# design.net
KiCad netlist of a schematic drawn in Altium Designer
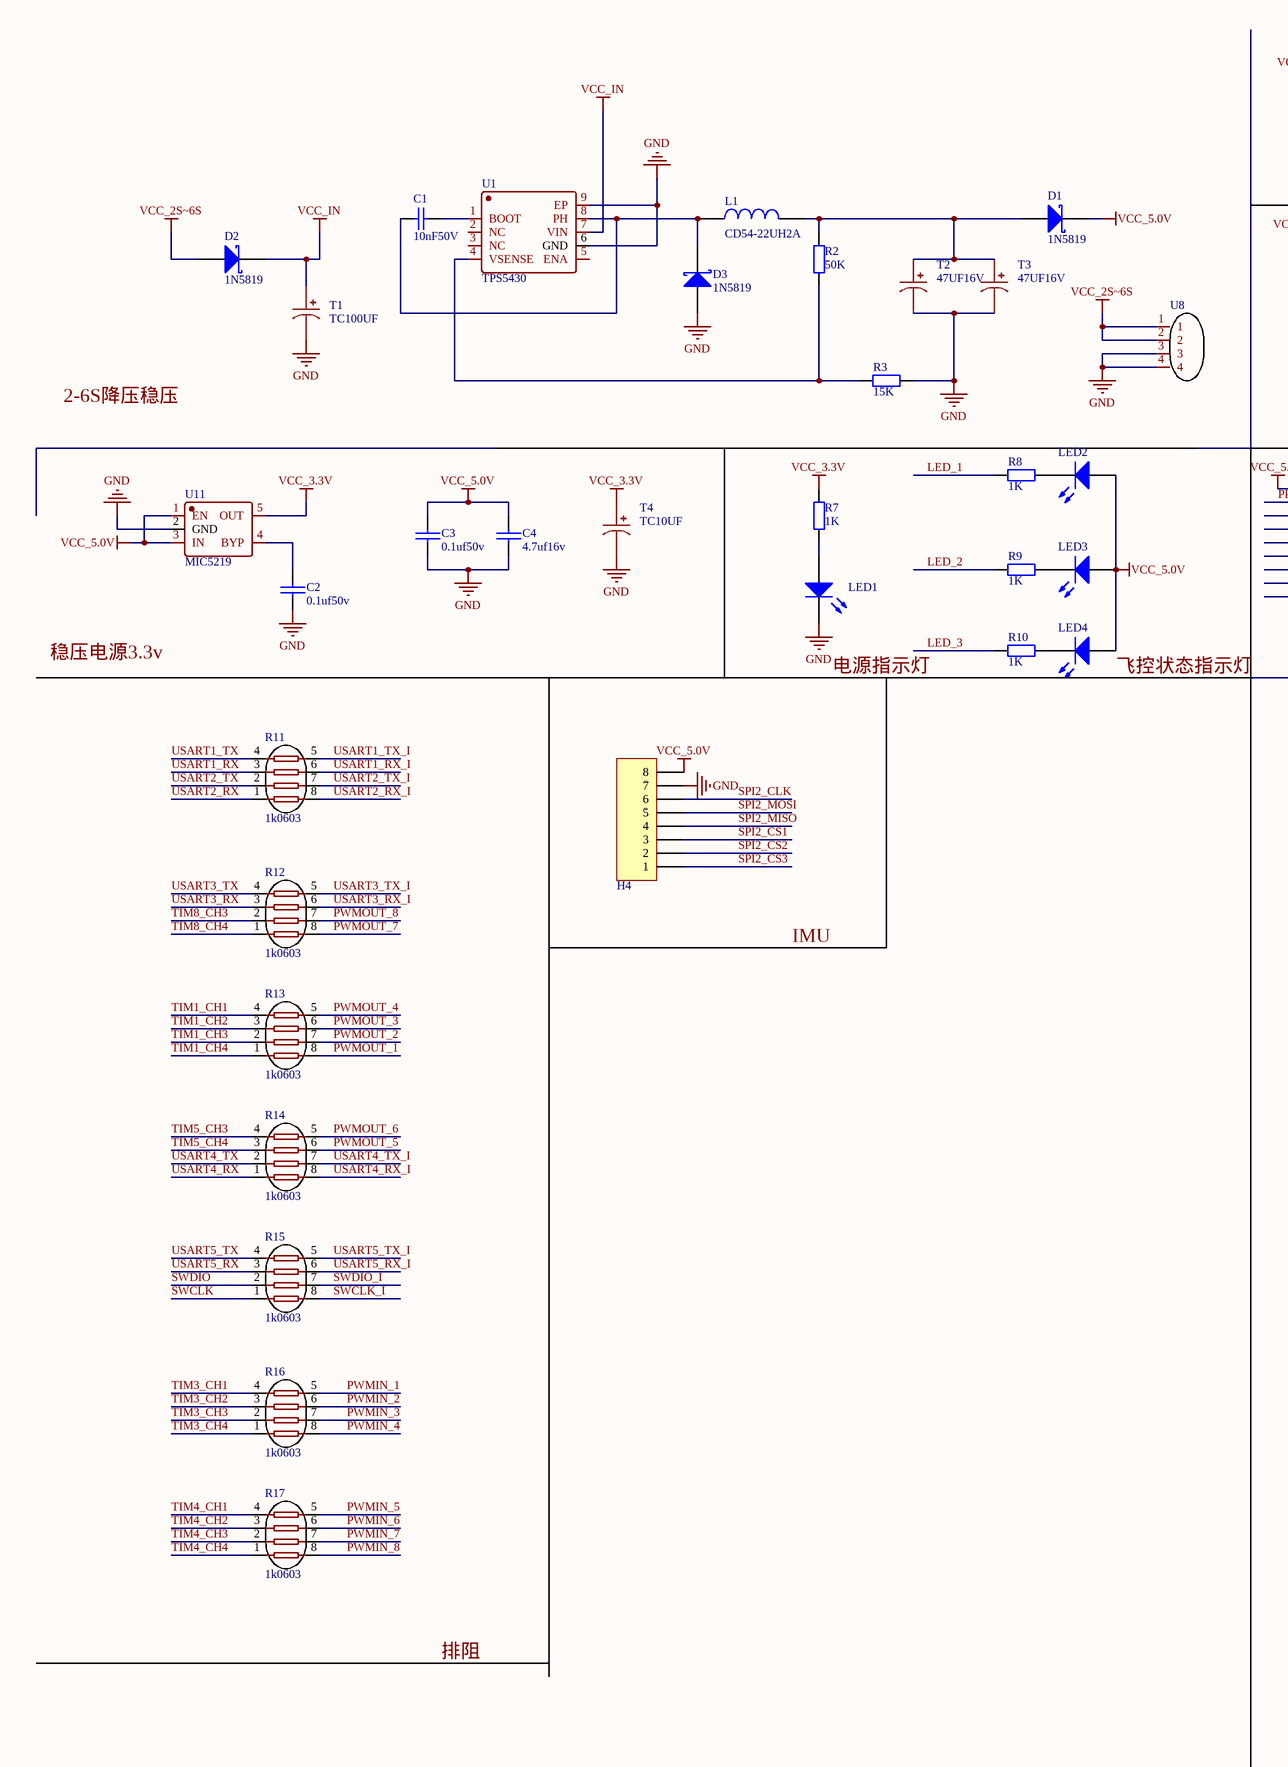
[diagram p0: 飞控板.SchDoc, left]
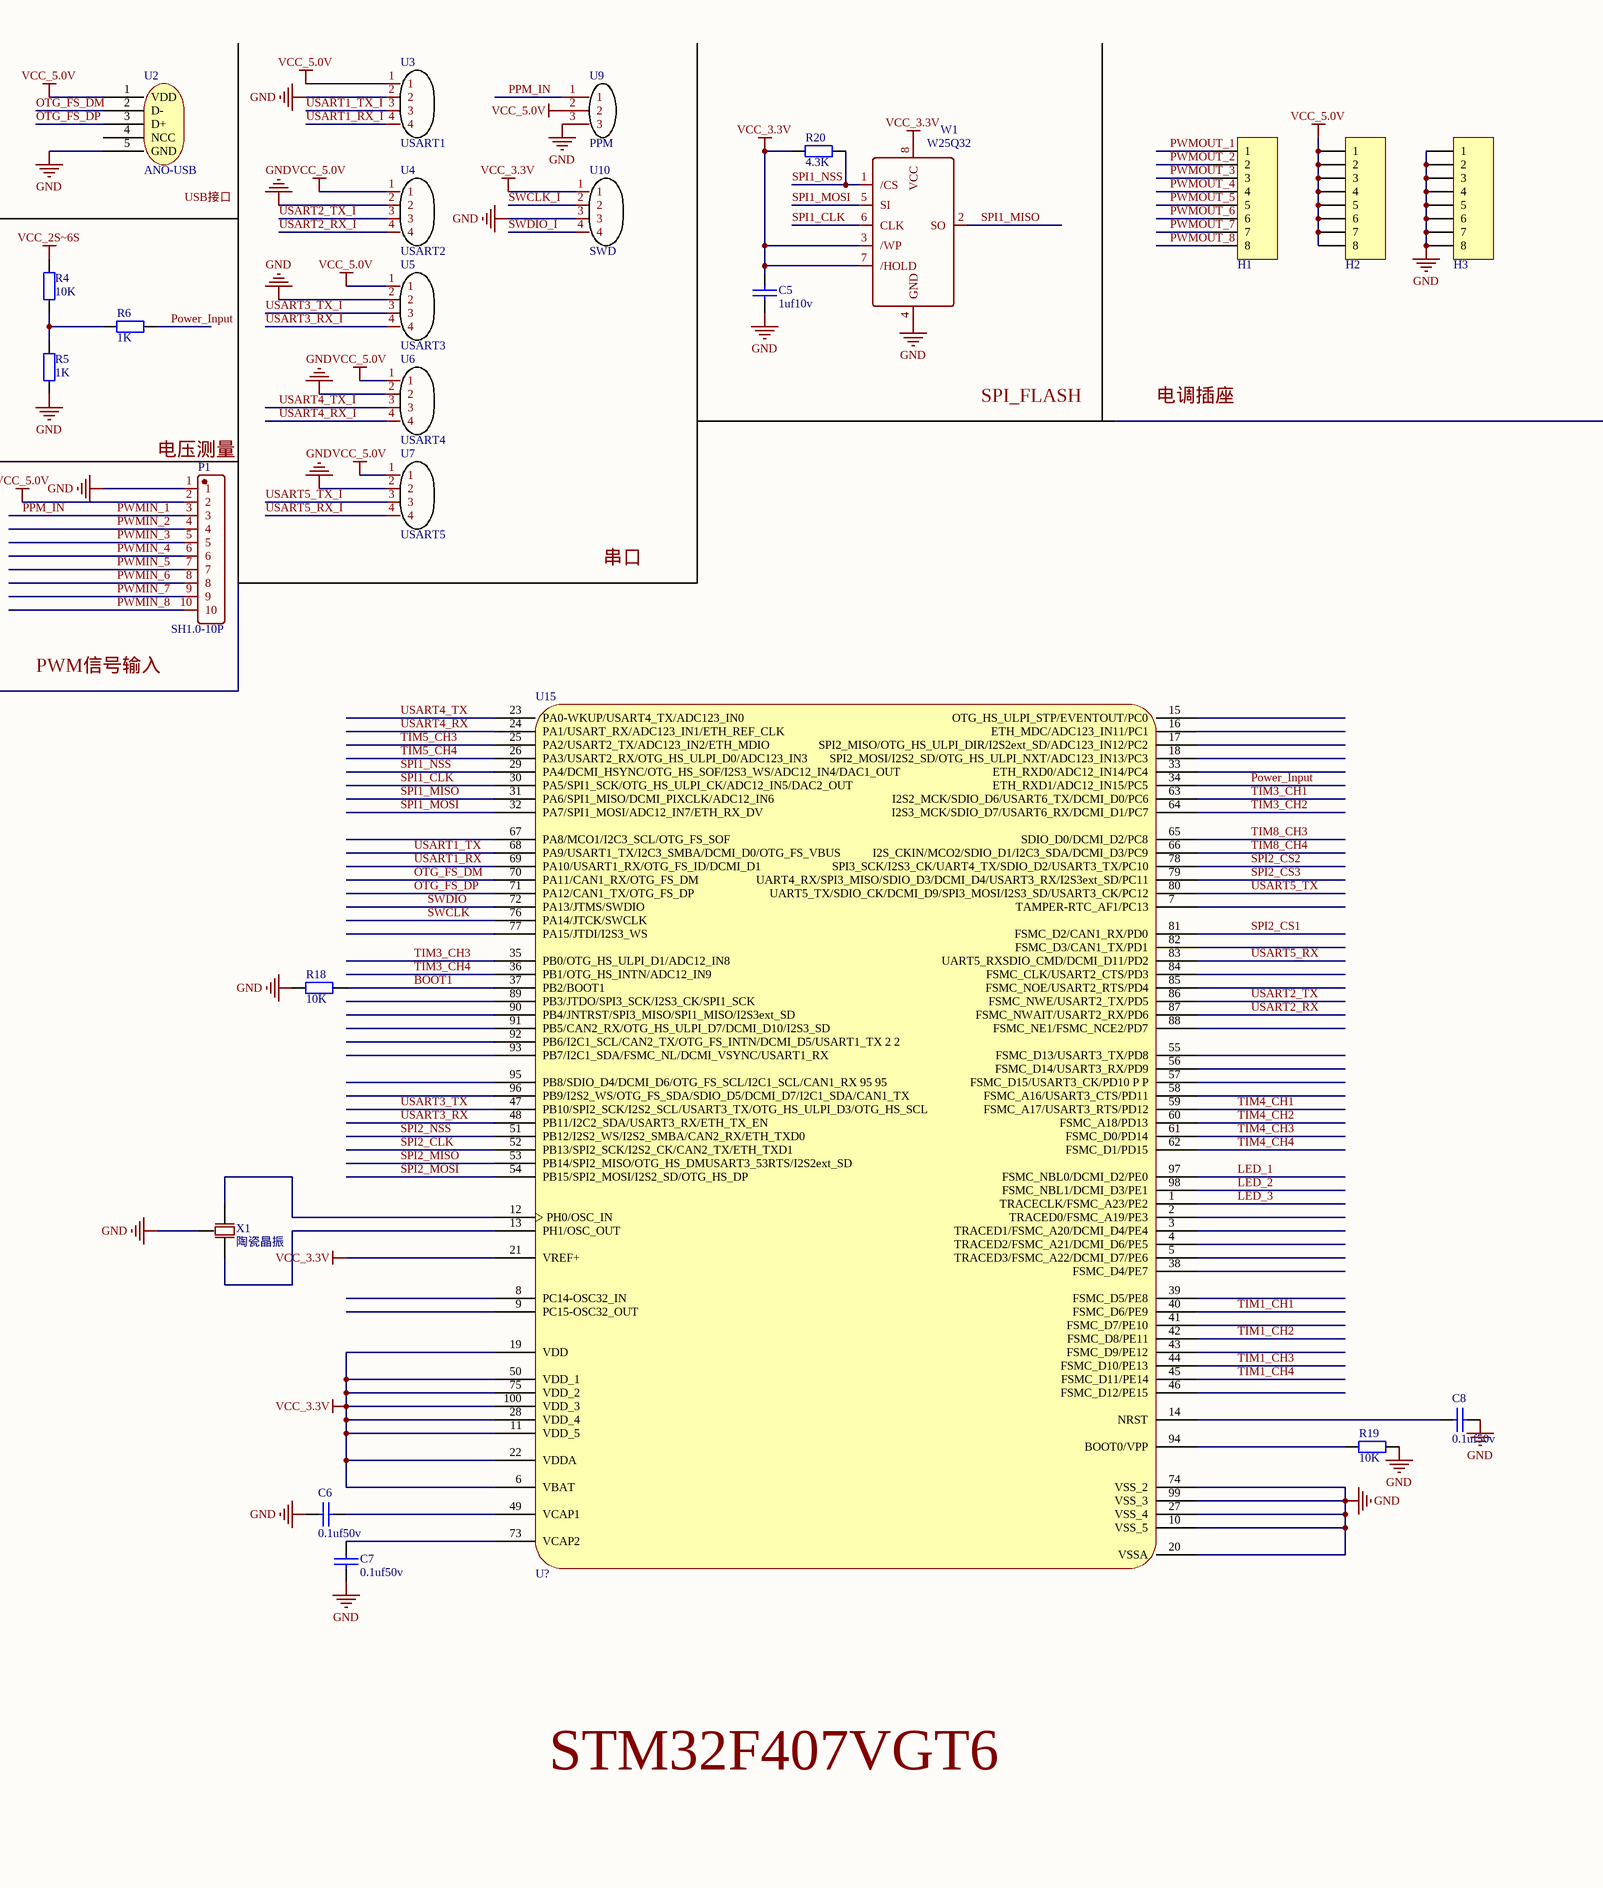
[diagram p1: 飞控板.SchDoc, right]

(export (version "E")
  (design (tool "Eeschema 10.0.6"))
  (components
    (comp (ref "C1")
      (value "10nF50V")
      (footprint "2512C")
      (description "2512瓷片电容")
      (libsource (lib "0.电阻电容电感") (part "Cap_2512"))
    )
    (comp (ref "C2")
      (value "0.1uf50v")
      (footprint "0805C")
      (description "无极性电容")
      (libsource (lib "电容") (part "CAP"))
    )
    (comp (ref "C3")
      (value "0.1uf50v")
      (footprint "0805C")
      (description "无极性电容")
      (libsource (lib "电容") (part "CAP"))
    )
    (comp (ref "C4")
      (value "4.7uf16v")
      (footprint "0805C")
      (description "无极性电容")
      (libsource (lib "电容") (part "CAP"))
    )
    (comp (ref "C5")
      (value "1uf10v")
      (footprint "0805C")
      (description "无极性电容")
      (libsource (lib "电容") (part "CAP"))
    )
    (comp (ref "C6")
      (value "0.1uf50v")
      (footprint "0805C")
      (description "无极性电容")
      (libsource (lib "电容") (part "CAP"))
    )
    (comp (ref "C7")
      (value "0.1uf50v")
      (footprint "0805C")
      (description "无极性电容")
      (libsource (lib "电容") (part "CAP"))
    )
    (comp (ref "C8")
      (value "0.1uf50v")
      (footprint "0805C")
      (description "无极性电容")
      (libsource (lib "电容") (part "CAP"))
    )
    (comp (ref "D1")
      (value "1N5819")
      (footprint "DO214AC_SMA")
      (description "贴片肖特基二极管")
      (libsource (lib "1.二极管") (part "1N5817-5819SMD"))
    )
    (comp (ref "D2")
      (value "1N5819")
      (footprint "DO214AC_SMA")
      (description "贴片肖特基二极管")
      (libsource (lib "1.二极管") (part "1N5817-5819SMD"))
    )
    (comp (ref "D3")
      (value "1N5819")
      (footprint "DO214AC_SMA")
      (description "贴片肖特基二极管")
      (libsource (lib "1.二极管") (part "1N5817-5819SMD"))
    )
    (comp (ref "H1")
      (value "Header 8")
      (footprint "HDR1X8")
      (description "Header, 8-Pin")
      (fields (field (name "PUBLISHER") "Altium Limited"))
      (libsource (lib "9.接插件 连接器") (part "Header 8"))
    )
    (comp (ref "H2")
      (value "Header 8")
      (footprint "HDR1X8")
      (description "Header, 8-Pin")
      (fields (field (name "PUBLISHER") "Altium Limited"))
      (libsource (lib "9.接插件 连接器") (part "Header 8"))
    )
    (comp (ref "H3")
      (value "Header 8")
      (footprint "HDR1X8")
      (description "Header, 8-Pin")
      (fields (field (name "PUBLISHER") "Altium Limited"))
      (libsource (lib "9.接插件 连接器") (part "Header 8"))
    )
    (comp (ref "H4")
      (value "Header 8")
      (footprint "HDR1X8")
      (description "Header, 8-Pin")
      (fields (field (name "PUBLISHER") "Altium Limited"))
      (libsource (lib "") (part "Header 8_1"))
    )
    (comp (ref "L1")
      (value "CD54-22UH2A")
      (footprint "CDRH73")
      (description "INDUCTOR")
      (libsource (lib "电感") (part "INDUCTOR"))
    )
    (comp (ref "LED1") (value "~") (footprint "LED-1206") (libsource (lib "1.二极管") (part "LED1206")))
    (comp (ref "LED2") (value "~") (footprint "LED-1206") (libsource (lib "1.二极管") (part "LED1206")))
    (comp (ref "LED3") (value "~") (footprint "LED-1206") (libsource (lib "1.二极管") (part "LED1206")))
    (comp (ref "LED4") (value "~") (footprint "LED-1206") (libsource (lib "1.二极管") (part "LED1206")))
    (comp (ref "P1")
      (value "SH1.0-10P")
      (footprint "SH1.0-10P")
      (libsource (lib "SH1.0-10P") (part "SH1.0-10P"))
    )
    (comp (ref "R2")
      (value "50K")
      (footprint "0805R")
      (description "0805贴片电阻")
      (libsource (lib "") (part "Res_0805_2"))
    )
    (comp (ref "R3")
      (value "15K")
      (footprint "0805R")
      (description "0805贴片电阻")
      (libsource (lib "0.电阻电容电感") (part "Res_0805"))
    )
    (comp (ref "R4")
      (value "10K")
      (footprint "0805R")
      (description "0805贴片电阻")
      (libsource (lib "") (part "Res_0805_2"))
    )
    (comp (ref "R5")
      (value "1K")
      (footprint "0805R")
      (description "0805贴片电阻")
      (libsource (lib "") (part "Res_0805_2"))
    )
    (comp (ref "R6")
      (value "1K")
      (footprint "0805R")
      (description "0805贴片电阻")
      (libsource (lib "0.电阻电容电感") (part "Res_0805"))
    )
    (comp (ref "R7")
      (value "1K")
      (footprint "0805R")
      (description "0805贴片电阻")
      (libsource (lib "") (part "Res_0805_2"))
    )
    (comp (ref "R8")
      (value "1K")
      (footprint "0805R")
      (description "0805贴片电阻")
      (libsource (lib "") (part "Res_0805_1"))
    )
    (comp (ref "R9")
      (value "1K")
      (footprint "0805R")
      (description "0805贴片电阻")
      (libsource (lib "") (part "Res_0805_1"))
    )
    (comp (ref "R10")
      (value "1K")
      (footprint "0805R")
      (description "0805贴片电阻")
      (libsource (lib "") (part "Res_0805_1"))
    )
    (comp (ref "R11") (value "1k0603") (footprint "1k0603") (libsource (lib "1k0603") (part "1k0603")))
    (comp (ref "R12") (value "1k0603") (footprint "1k0603") (libsource (lib "1k0603") (part "1k0603")))
    (comp (ref "R13") (value "1k0603") (footprint "1k0603") (libsource (lib "1k0603") (part "1k0603")))
    (comp (ref "R14") (value "1k0603") (footprint "1k0603") (libsource (lib "1k0603") (part "1k0603")))
    (comp (ref "R15") (value "1k0603") (footprint "1k0603") (libsource (lib "1k0603") (part "1k0603")))
    (comp (ref "R16") (value "1k0603") (footprint "1k0603") (libsource (lib "1k0603") (part "1k0603")))
    (comp (ref "R17") (value "1k0603") (footprint "1k0603") (libsource (lib "1k0603") (part "1k0603")))
    (comp (ref "R18")
      (value "10K")
      (footprint "0805R")
      (description "0805贴片电阻")
      (libsource (lib "") (part "Res_0805_1"))
    )
    (comp (ref "R19")
      (value "10K")
      (footprint "0805R")
      (description "0805贴片电阻")
      (libsource (lib "") (part "Res_0805_1"))
    )
    (comp (ref "R20")
      (value "4.3K")
      (footprint "0805R")
      (description "0805贴片电阻")
      (libsource (lib "") (part "Res_0805_1"))
    )
    (comp (ref "T1") (value "TC100UF") (footprint "TC100UF") (libsource (lib "TC100UF") (part "TC100UF")))
    (comp (ref "T2") (value "47UF16V") (footprint "47UF16V") (libsource (lib "钽电容47uf16v") (part "47UF16V")))
    (comp (ref "T3") (value "47UF16V") (footprint "47UF16V") (libsource (lib "钽电容47uf16v") (part "47UF16V")))
    (comp (ref "T4") (value "TC10UF") (footprint "TC10UF") (libsource (lib "TC10UF") (part "TC10UF")))
    (comp (ref "U1") (value "TPS5430") (footprint "TPS5430") (libsource (lib "TPS5430") (part "TPS5430")))
    (comp (ref "U2") (value "ANO-USB") (footprint "ANO-USB") (libsource (lib "ANO-USB") (part "ANO-USB")))
    (comp (ref "U3") (value "USART1") (footprint "SH1.0-4P") (libsource (lib "SH1.0-4P") (part "SH1.0-4P")))
    (comp (ref "U4") (value "USART2") (footprint "SH1.0-4P") (libsource (lib "SH1.0-4P") (part "SH1.0-4P")))
    (comp (ref "U5") (value "USART3") (footprint "SH1.0-4P") (libsource (lib "SH1.0-4P") (part "SH1.0-4P")))
    (comp (ref "U6") (value "USART4") (footprint "SH1.0-4P") (libsource (lib "SH1.0-4P") (part "SH1.0-4P")))
    (comp (ref "U7") (value "USART5") (footprint "SH1.0-4P") (libsource (lib "SH1.0-4P") (part "SH1.0-4P")))
    (comp (ref "U8") (value "~") (footprint "SH1.0-4P") (libsource (lib "SH1.0-4P") (part "SH1.0-4P")))
    (comp (ref "U9") (value "PPM") (footprint "SH1.0-3P") (libsource (lib "SH1.0-3P") (part "SH1.0-3P")))
    (comp (ref "U10") (value "SWD") (footprint "SH1.0-4P") (libsource (lib "SH1.0-4P") (part "SH1.0-4P")))
    (comp (ref "U11") (value "MIC5219") (footprint "MIC5219") (libsource (lib "MIC5219") (part "MIC5219")))
    (comp (ref "U15")
      (value "U?")
      (footprint "STM32F407VGT6=")
      (libsource (lib "STM32F407VGT6=") (part "STM32F407VGT6="))
    )
    (comp (ref "W1") (value "W25Q32") (footprint "W25Q32") (libsource (lib "W25Q32") (part "W25Q32")))
    (comp (ref "X1") (value "陶瓷晶振") (footprint "陶瓷晶振") (libsource (lib "陶瓷晶振") (part "陶瓷晶振")))
  )
  (nets
    (net (code "2") (name "/BOOT1") (class "Default")
      (node (ref "R18") (pin "1") (pinfunction "1_1") (pintype "passive"))
      (node (ref "U15") (pin "37") (pinfunction "PB2/BOOT1_37") (pintype "passive"))
    )
    (net (code "4") (name "/LED_1") (class "Default")
      (node (ref "R8") (pin "2") (pinfunction "2_2") (pintype "passive"))
      (node (ref "U15") (pin "97") (pinfunction "FSMC_NBL0/DCMI_D2/PE0_97") (pintype "passive"))
    )
    (net (code "5") (name "/LED_2") (class "Default")
      (node (ref "R9") (pin "2") (pinfunction "2_2") (pintype "passive"))
      (node (ref "U15") (pin "98") (pinfunction "FSMC_NBL1/DCMI_D3/PE1_98") (pintype "passive"))
    )
    (net (code "6") (name "/LED_3") (class "Default")
      (node (ref "R10") (pin "2") (pinfunction "2_2") (pintype "passive"))
      (node (ref "U15") (pin "1") (pinfunction "TRACECLK/FSMC_A23/PE2_1") (pintype "passive"))
    )
    (net (code "7") (name "/OTG_FS_DM") (class "Default")
      (node (ref "U15") (pin "70") (pinfunction "PA11/CAN1_RX/OTG_FS_DM_70") (pintype "passive"))
      (node (ref "U2") (pin "2") (pinfunction "D-_2") (pintype "passive"))
    )
    (net (code "8") (name "/OTG_FS_DP") (class "Default")
      (node (ref "U15") (pin "71") (pinfunction "PA12/CAN1_TX/OTG_FS_DP_71") (pintype "passive"))
      (node (ref "U2") (pin "3") (pinfunction "D+_3") (pintype "passive"))
    )
    (net (code "9") (name "/PPM_IN") (class "Default")
      (node (ref "P1") (pin "3") (pinfunction "3_3") (pintype "passive"))
      (node (ref "R16") (pin "5") (pinfunction "5_5") (pintype "passive"))
      (node (ref "U9") (pin "1") (pinfunction "1_1") (pintype "passive"))
    )
    (net (code "10") (name "/PWMIN_2") (class "Default")
      (node (ref "P1") (pin "4") (pinfunction "4_4") (pintype "passive"))
      (node (ref "R16") (pin "6") (pinfunction "6_6") (pintype "passive"))
    )
    (net (code "11") (name "/PWMIN_3") (class "Default")
      (node (ref "P1") (pin "5") (pinfunction "5_5") (pintype "passive"))
      (node (ref "R16") (pin "7") (pinfunction "7_7") (pintype "passive"))
    )
    (net (code "12") (name "/PWMIN_4") (class "Default")
      (node (ref "P1") (pin "6") (pinfunction "6_6") (pintype "passive"))
      (node (ref "R16") (pin "8") (pinfunction "8_8") (pintype "passive"))
    )
    (net (code "13") (name "/PWMIN_5") (class "Default")
      (node (ref "P1") (pin "7") (pinfunction "7_7") (pintype "passive"))
      (node (ref "R17") (pin "5") (pinfunction "5_5") (pintype "passive"))
    )
    (net (code "14") (name "/PWMIN_6") (class "Default")
      (node (ref "P1") (pin "8") (pinfunction "8_8") (pintype "passive"))
      (node (ref "R17") (pin "6") (pinfunction "6_6") (pintype "passive"))
    )
    (net (code "15") (name "/PWMIN_7") (class "Default")
      (node (ref "P1") (pin "9") (pinfunction "9_9") (pintype "passive"))
      (node (ref "R17") (pin "7") (pinfunction "7_7") (pintype "passive"))
    )
    (net (code "16") (name "/PWMIN_8") (class "Default")
      (node (ref "P1") (pin "10") (pinfunction "10_10") (pintype "passive"))
      (node (ref "R17") (pin "8") (pinfunction "8_8") (pintype "passive"))
    )
    (net (code "17") (name "/PWMOUT_1") (class "Default")
      (node (ref "H1") (pin "1") (pinfunction "1_1") (pintype "passive"))
      (node (ref "R13") (pin "8") (pinfunction "8_8") (pintype "passive"))
    )
    (net (code "18") (name "/PWMOUT_2") (class "Default")
      (node (ref "H1") (pin "2") (pinfunction "2_2") (pintype "passive"))
      (node (ref "R13") (pin "7") (pinfunction "7_7") (pintype "passive"))
    )
    (net (code "19") (name "/PWMOUT_3") (class "Default")
      (node (ref "H1") (pin "3") (pinfunction "3_3") (pintype "passive"))
      (node (ref "R13") (pin "6") (pinfunction "6_6") (pintype "passive"))
    )
    (net (code "20") (name "/PWMOUT_4") (class "Default")
      (node (ref "H1") (pin "4") (pinfunction "4_4") (pintype "passive"))
      (node (ref "R13") (pin "5") (pinfunction "5_5") (pintype "passive"))
    )
    (net (code "21") (name "/PWMOUT_5") (class "Default")
      (node (ref "H1") (pin "5") (pinfunction "5_5") (pintype "passive"))
      (node (ref "R14") (pin "6") (pinfunction "6_6") (pintype "passive"))
    )
    (net (code "22") (name "/PWMOUT_6") (class "Default")
      (node (ref "H1") (pin "6") (pinfunction "6_6") (pintype "passive"))
      (node (ref "R14") (pin "5") (pinfunction "5_5") (pintype "passive"))
    )
    (net (code "23") (name "/PWMOUT_7") (class "Default")
      (node (ref "H1") (pin "7") (pinfunction "7_7") (pintype "passive"))
      (node (ref "R12") (pin "8") (pinfunction "8_8") (pintype "passive"))
    )
    (net (code "24") (name "/PWMOUT_8") (class "Default")
      (node (ref "H1") (pin "8") (pinfunction "8_8") (pintype "passive"))
      (node (ref "R12") (pin "7") (pinfunction "7_7") (pintype "passive"))
    )
    (net (code "26") (name "/Power_Input") (class "Default")
      (node (ref "R6") (pin "2") (pinfunction "2_2") (pintype "passive"))
      (node (ref "U15") (pin "34") (pinfunction "ETH_RXD1/ADC12_IN15/PC5_34") (pintype "passive"))
    )
    (net (code "27") (name "/SPI1_CLK") (class "Default")
      (node (ref "U15") (pin "30") (pinfunction "PA5/SPI1_SCK/OTG_HS_ULPI_CK/ADC12_IN5/DAC2_OUT_30") (pintype "passive"))
      (node (ref "W1") (pin "6") (pinfunction "CLK_6") (pintype "passive"))
    )
    (net (code "28") (name "/SPI1_MISO") (class "Default")
      (node (ref "U15") (pin "31") (pinfunction "PA6/SPI1_MISO/DCMI_PIXCLK/ADC12_IN6_31") (pintype "passive"))
      (node (ref "W1") (pin "2") (pinfunction "SO_2") (pintype "passive"))
    )
    (net (code "29") (name "/SPI1_MOSI") (class "Default")
      (node (ref "U15") (pin "32") (pinfunction "PA7/SPI1_MOSI/ADC12_IN7/ETH_RX_DV_32") (pintype "passive"))
      (node (ref "W1") (pin "5") (pinfunction "SI_5") (pintype "passive"))
    )
    (net (code "30") (name "/SPI1_NSS") (class "Default")
      (node (ref "R20") (pin "1") (pinfunction "1_1") (pintype "passive"))
      (node (ref "U15") (pin "29") (pinfunction "PA4/DCMI_HSYNC/OTG_HS_SOF/I2S3_WS/ADC12_IN4/DAC1_OUT_29") (pintype "passive"))
      (node (ref "W1") (pin "1") (pinfunction "/CS_1") (pintype "passive"))
    )
    (net (code "31") (name "/SPI2_CLK") (class "Default")
      (node (ref "H4") (pin "6") (pinfunction "6_6") (pintype "passive"))
      (node (ref "U15") (pin "52") (pinfunction "PB13/SPI2_SCK/I2S2_CK/CAN2_TX/ETH_TXD1_52") (pintype "passive"))
    )
    (net (code "32") (name "/SPI2_CS1") (class "Default")
      (node (ref "H4") (pin "3") (pinfunction "3_3") (pintype "passive"))
      (node (ref "U15") (pin "81") (pinfunction "FSMC_D2/CAN1_RX/PD0_81") (pintype "passive"))
    )
    (net (code "33") (name "/SPI2_CS2") (class "Default")
      (node (ref "H4") (pin "2") (pinfunction "2_2") (pintype "passive"))
      (node (ref "U15") (pin "78") (pinfunction "SPI3_SCK/I2S3_CK/UART4_TX/SDIO_D2/USART3_TX/PC10_78") (pintype "passive"))
    )
    (net (code "34") (name "/SPI2_CS3") (class "Default")
      (node (ref "H4") (pin "1") (pinfunction "1_1") (pintype "passive"))
      (node (ref "U15") (pin "79") (pinfunction "UART4_RX/SPI3_MISO/SDIO_D3/DCMI_D4/USART3_RX/I2S3ext_SD/PC11_79") (pintype "passive"))
    )
    (net (code "35") (name "/SPI2_MISO") (class "Default")
      (node (ref "H4") (pin "4") (pinfunction "4_4") (pintype "passive"))
      (node (ref "U15") (pin "53") (pinfunction "PB14/SPI2_MISO/OTG_HS_DMUSART3_53RTS/I2S2ext_SD_53") (pintype "passive"))
    )
    (net (code "36") (name "/SPI2_MOSI") (class "Default")
      (node (ref "H4") (pin "5") (pinfunction "5_5") (pintype "passive"))
      (node (ref "U15") (pin "54") (pinfunction "PB15/SPI2_MOSI/I2S2_SD/OTG_HS_DP_54") (pintype "passive"))
    )
    (net (code "37") (name "/SPI2_NSS") (class "Default")
      (node (ref "U15") (pin "51") (pinfunction "PB12/I2S2_WS/I2S2_SMBA/CAN2_RX/ETH_TXD0_51") (pintype "passive"))
    )
    (net (code "40") (name "/SWCLK") (class "Default")
      (node (ref "R15") (pin "1") (pinfunction "1_1") (pintype "passive"))
      (node (ref "U15") (pin "76") (pinfunction "PA14/JTCK/SWCLK_76") (pintype "passive"))
    )
    (net (code "41") (name "/SWCLK_I") (class "Default")
      (node (ref "R15") (pin "8") (pinfunction "8_8") (pintype "passive"))
      (node (ref "U10") (pin "2") (pinfunction "2_2") (pintype "passive"))
    )
    (net (code "42") (name "/SWDIO") (class "Default")
      (node (ref "R15") (pin "2") (pinfunction "2_2") (pintype "passive"))
      (node (ref "U15") (pin "72") (pinfunction "PA13/JTMS/SWDIO_72") (pintype "passive"))
    )
    (net (code "43") (name "/SWDIO_I") (class "Default")
      (node (ref "R15") (pin "7") (pinfunction "7_7") (pintype "passive"))
      (node (ref "U10") (pin "4") (pinfunction "4_4") (pintype "passive"))
    )
    (net (code "44") (name "/TIM1_CH1") (class "Default")
      (node (ref "R13") (pin "4") (pinfunction "4_4") (pintype "passive"))
      (node (ref "U15") (pin "40") (pinfunction "FSMC_D6/PE9_40") (pintype "passive"))
    )
    (net (code "45") (name "/TIM1_CH2") (class "Default")
      (node (ref "R13") (pin "3") (pinfunction "3_3") (pintype "passive"))
      (node (ref "U15") (pin "42") (pinfunction "FSMC_D8/PE11_42") (pintype "passive"))
    )
    (net (code "46") (name "/TIM1_CH3") (class "Default")
      (node (ref "R13") (pin "2") (pinfunction "2_2") (pintype "passive"))
      (node (ref "U15") (pin "44") (pinfunction "FSMC_D10/PE13_44") (pintype "passive"))
    )
    (net (code "47") (name "/TIM1_CH4") (class "Default")
      (node (ref "R13") (pin "1") (pinfunction "1_1") (pintype "passive"))
      (node (ref "U15") (pin "45") (pinfunction "FSMC_D11/PE14_45") (pintype "passive"))
    )
    (net (code "48") (name "/TIM3_CH1") (class "Default")
      (node (ref "R16") (pin "4") (pinfunction "4_4") (pintype "passive"))
      (node (ref "U15") (pin "63") (pinfunction "I2S2_MCK/SDIO_D6/USART6_TX/DCMI_D0/PC6_63") (pintype "passive"))
    )
    (net (code "49") (name "/TIM3_CH2") (class "Default")
      (node (ref "R16") (pin "3") (pinfunction "3_3") (pintype "passive"))
      (node (ref "U15") (pin "64") (pinfunction "I2S3_MCK/SDIO_D7/USART6_RX/DCMI_D1/PC7_64") (pintype "passive"))
    )
    (net (code "50") (name "/TIM3_CH3") (class "Default")
      (node (ref "R16") (pin "2") (pinfunction "2_2") (pintype "passive"))
      (node (ref "U15") (pin "35") (pinfunction "PB0/OTG_HS_ULPI_D1/ADC12_IN8_35") (pintype "passive"))
    )
    (net (code "51") (name "/TIM3_CH4") (class "Default")
      (node (ref "R16") (pin "1") (pinfunction "1_1") (pintype "passive"))
      (node (ref "U15") (pin "36") (pinfunction "PB1/OTG_HS_INTN/ADC12_IN9_36") (pintype "passive"))
    )
    (net (code "52") (name "/TIM4_CH1") (class "Default")
      (node (ref "R17") (pin "4") (pinfunction "4_4") (pintype "passive"))
      (node (ref "U15") (pin "59") (pinfunction "FSMC_A17/USART3_RTS/PD12_59") (pintype "passive"))
    )
    (net (code "53") (name "/TIM4_CH2") (class "Default")
      (node (ref "R17") (pin "3") (pinfunction "3_3") (pintype "passive"))
      (node (ref "U15") (pin "60") (pinfunction "FSMC_A18/PD13_60") (pintype "passive"))
    )
    (net (code "54") (name "/TIM4_CH3") (class "Default")
      (node (ref "R17") (pin "2") (pinfunction "2_2") (pintype "passive"))
      (node (ref "U15") (pin "61") (pinfunction "FSMC_D0/PD14_61") (pintype "passive"))
    )
    (net (code "55") (name "/TIM4_CH4") (class "Default")
      (node (ref "R17") (pin "1") (pinfunction "1_1") (pintype "passive"))
      (node (ref "U15") (pin "62") (pinfunction "FSMC_D1/PD15_62") (pintype "passive"))
    )
    (net (code "56") (name "/TIM5_CH3") (class "Default")
      (node (ref "R14") (pin "4") (pinfunction "4_4") (pintype "passive"))
      (node (ref "U15") (pin "25") (pinfunction "PA2/USART2_TX/ADC123_IN2/ETH_MDIO_25") (pintype "passive"))
    )
    (net (code "57") (name "/TIM5_CH4") (class "Default")
      (node (ref "R14") (pin "3") (pinfunction "3_3") (pintype "passive"))
      (node (ref "U15") (pin "26") (pinfunction "PA3/USART2_RX/OTG_HS_ULPI_D0/ADC123_IN3_26") (pintype "passive"))
    )
    (net (code "58") (name "/TIM8_CH3") (class "Default")
      (node (ref "R12") (pin "2") (pinfunction "2_2") (pintype "passive"))
      (node (ref "U15") (pin "65") (pinfunction "SDIO_D0/DCMI_D2/PC8_65") (pintype "passive"))
    )
    (net (code "59") (name "/TIM8_CH4") (class "Default")
      (node (ref "R12") (pin "1") (pinfunction "1_1") (pintype "passive"))
      (node (ref "U15") (pin "66") (pinfunction "I2S_CKIN/MCO2/SDIO_D1/I2C3_SDA/DCMI_D3/PC9_66") (pintype "passive"))
    )
    (net (code "60") (name "/USART1_RX") (class "Default")
      (node (ref "R11") (pin "3") (pinfunction "3_3") (pintype "passive"))
      (node (ref "U15") (pin "69") (pinfunction "PA10/USART1_RX/OTG_FS_ID/DCMI_D1_69") (pintype "passive"))
    )
    (net (code "61") (name "/USART1_RX_I") (class "Default")
      (node (ref "R11") (pin "6") (pinfunction "6_6") (pintype "passive"))
      (node (ref "U3") (pin "4") (pinfunction "4_4") (pintype "passive"))
    )
    (net (code "62") (name "/USART1_TX") (class "Default")
      (node (ref "R11") (pin "4") (pinfunction "4_4") (pintype "passive"))
      (node (ref "U15") (pin "68") (pinfunction "PA9/USART1_TX/I2C3_SMBA/DCMI_D0/OTG_FS_VBUS_68") (pintype "passive"))
    )
    (net (code "63") (name "/USART1_TX_I") (class "Default")
      (node (ref "R11") (pin "5") (pinfunction "5_5") (pintype "passive"))
      (node (ref "U3") (pin "3") (pinfunction "3_3") (pintype "passive"))
    )
    (net (code "64") (name "/USART2_RX") (class "Default")
      (node (ref "R11") (pin "1") (pinfunction "1_1") (pintype "passive"))
      (node (ref "U15") (pin "87") (pinfunction "FSMC_NWAIT/USART2_RX/PD6_87") (pintype "passive"))
    )
    (net (code "65") (name "/USART2_RX_I") (class "Default")
      (node (ref "R11") (pin "8") (pinfunction "8_8") (pintype "passive"))
      (node (ref "U4") (pin "4") (pinfunction "4_4") (pintype "passive"))
    )
    (net (code "66") (name "/USART2_TX") (class "Default")
      (node (ref "R11") (pin "2") (pinfunction "2_2") (pintype "passive"))
      (node (ref "U15") (pin "86") (pinfunction "FSMC_NWE/USART2_TX/PD5_86") (pintype "passive"))
    )
    (net (code "67") (name "/USART2_TX_I") (class "Default")
      (node (ref "R11") (pin "7") (pinfunction "7_7") (pintype "passive"))
      (node (ref "U4") (pin "3") (pinfunction "3_3") (pintype "passive"))
    )
    (net (code "68") (name "/USART3_RX") (class "Default")
      (node (ref "R12") (pin "3") (pinfunction "3_3") (pintype "passive"))
      (node (ref "U15") (pin "48") (pinfunction "PB11/I2C2_SDA/USART3_RX/ETH_TX_EN_48") (pintype "passive"))
    )
    (net (code "69") (name "/USART3_RX_I") (class "Default")
      (node (ref "R12") (pin "6") (pinfunction "6_6") (pintype "passive"))
      (node (ref "U5") (pin "4") (pinfunction "4_4") (pintype "passive"))
    )
    (net (code "70") (name "/USART3_TX") (class "Default")
      (node (ref "R12") (pin "4") (pinfunction "4_4") (pintype "passive"))
      (node (ref "U15") (pin "47") (pinfunction "PB10/SPI2_SCK/I2S2_SCL/USART3_TX/OTG_HS_ULPI_D3/OTG_HS_SCL_47") (pintype "passive"))
    )
    (net (code "71") (name "/USART3_TX_I") (class "Default")
      (node (ref "R12") (pin "5") (pinfunction "5_5") (pintype "passive"))
      (node (ref "U5") (pin "3") (pinfunction "3_3") (pintype "passive"))
    )
    (net (code "72") (name "/USART4_RX") (class "Default")
      (node (ref "R14") (pin "1") (pinfunction "1_1") (pintype "passive"))
      (node (ref "U15") (pin "24") (pinfunction "PA1/USART_RX/ADC123_IN1/ETH_REF_CLK_24") (pintype "passive"))
    )
    (net (code "73") (name "/USART4_RX_I") (class "Default")
      (node (ref "R14") (pin "8") (pinfunction "8_8") (pintype "passive"))
      (node (ref "U6") (pin "4") (pinfunction "4_4") (pintype "passive"))
    )
    (net (code "74") (name "/USART4_TX") (class "Default")
      (node (ref "R14") (pin "2") (pinfunction "2_2") (pintype "passive"))
      (node (ref "U15") (pin "23") (pinfunction "PA0-WKUP/USART4_TX/ADC123_IN0_23") (pintype "passive"))
    )
    (net (code "75") (name "/USART4_TX_I") (class "Default")
      (node (ref "R14") (pin "7") (pinfunction "7_7") (pintype "passive"))
      (node (ref "U6") (pin "3") (pinfunction "3_3") (pintype "passive"))
    )
    (net (code "76") (name "/USART5_RX") (class "Default")
      (node (ref "R15") (pin "3") (pinfunction "3_3") (pintype "passive"))
      (node (ref "U15") (pin "83") (pinfunction "UART5_RXSDIO_CMD/DCMI_D11/PD2_83") (pintype "passive"))
    )
    (net (code "77") (name "/USART5_RX_I") (class "Default")
      (node (ref "R15") (pin "6") (pinfunction "6_6") (pintype "passive"))
      (node (ref "U7") (pin "4") (pinfunction "4_4") (pintype "passive"))
    )
    (net (code "78") (name "/USART5_TX") (class "Default")
      (node (ref "R15") (pin "4") (pinfunction "4_4") (pintype "passive"))
      (node (ref "U15") (pin "80") (pinfunction "UART5_TX/SDIO_CK/DCMI_D9/SPI3_MOSI/I2S3_SD/USART3_CK/PC12_80") (pintype "passive"))
    )
    (net (code "79") (name "/USART5_TX_I") (class "Default")
      (node (ref "R15") (pin "5") (pinfunction "5_5") (pintype "passive"))
      (node (ref "U7") (pin "3") (pinfunction "3_3") (pintype "passive"))
    )
    (net (code "88") (name "GND") (class "Default")
      (node (ref "C2") (pin "1") (pinfunction "1_1") (pintype "passive"))
      (node (ref "C3") (pin "1") (pinfunction "1_1") (pintype "passive"))
      (node (ref "C4") (pin "1") (pinfunction "1_1") (pintype "passive"))
      (node (ref "C5") (pin "1") (pinfunction "1_1") (pintype "passive"))
      (node (ref "C6") (pin "1") (pinfunction "1_1") (pintype "passive"))
      (node (ref "C7") (pin "1") (pinfunction "1_1") (pintype "passive"))
      (node (ref "C8") (pin "2") (pinfunction "2_2") (pintype "passive"))
      (node (ref "D3") (pin "1") (pinfunction "A_1") (pintype "passive"))
      (node (ref "H3") (pin "1") (pinfunction "1_1") (pintype "passive"))
      (node (ref "H3") (pin "2") (pinfunction "2_2") (pintype "passive"))
      (node (ref "H3") (pin "3") (pinfunction "3_3") (pintype "passive"))
      (node (ref "H3") (pin "4") (pinfunction "4_4") (pintype "passive"))
      (node (ref "H3") (pin "5") (pinfunction "5_5") (pintype "passive"))
      (node (ref "H3") (pin "6") (pinfunction "6_6") (pintype "passive"))
      (node (ref "H3") (pin "7") (pinfunction "7_7") (pintype "passive"))
      (node (ref "H3") (pin "8") (pinfunction "8_8") (pintype "passive"))
      (node (ref "H4") (pin "7") (pinfunction "7_7") (pintype "passive"))
      (node (ref "LED1") (pin "2") (pinfunction "K_2") (pintype "passive"))
      (node (ref "P1") (pin "1") (pinfunction "1_1") (pintype "passive"))
      (node (ref "R18") (pin "2") (pinfunction "2_2") (pintype "passive"))
      (node (ref "R19") (pin "1") (pinfunction "1_1") (pintype "passive"))
      (node (ref "R3") (pin "2") (pinfunction "2_2") (pintype "passive"))
      (node (ref "R5") (pin "2") (pinfunction "2_2") (pintype "passive"))
      (node (ref "T1") (pin "2") (pinfunction "2_2") (pintype "passive"))
      (node (ref "T2") (pin "2") (pinfunction "2_2") (pintype "passive"))
      (node (ref "T3") (pin "2") (pinfunction "2_2") (pintype "passive"))
      (node (ref "T4") (pin "2") (pinfunction "2_2") (pintype "passive"))
      (node (ref "U1") (pin "6") (pinfunction "GND_6") (pintype "passive"))
      (node (ref "U1") (pin "9") (pinfunction "EP_9") (pintype "passive"))
      (node (ref "U10") (pin "3") (pinfunction "3_3") (pintype "passive"))
      (node (ref "U11") (pin "2") (pinfunction "GND_2") (pintype "passive"))
      (node (ref "U15") (pin "10") (pinfunction "VSS_5_10") (pintype "passive"))
      (node (ref "U15") (pin "20") (pinfunction "VSSA_20") (pintype "passive"))
      (node (ref "U15") (pin "27") (pinfunction "VSS_4_27") (pintype "passive"))
      (node (ref "U15") (pin "74") (pinfunction "VSS_2_74") (pintype "passive"))
      (node (ref "U15") (pin "99") (pinfunction "VSS_3_99") (pintype "passive"))
      (node (ref "U2") (pin "5") (pinfunction "GND_5") (pintype "passive"))
      (node (ref "U3") (pin "2") (pinfunction "2_2") (pintype "passive"))
      (node (ref "U4") (pin "2") (pinfunction "2_2") (pintype "passive"))
      (node (ref "U5") (pin "2") (pinfunction "2_2") (pintype "passive"))
      (node (ref "U6") (pin "2") (pinfunction "2_2") (pintype "passive"))
      (node (ref "U7") (pin "2") (pinfunction "2_2") (pintype "passive"))
      (node (ref "U8") (pin "3") (pinfunction "3_3") (pintype "passive"))
      (node (ref "U8") (pin "4") (pinfunction "4_4") (pintype "passive"))
      (node (ref "U9") (pin "3") (pinfunction "3_3") (pintype "passive"))
      (node (ref "W1") (pin "4") (pinfunction "GND_4") (pintype "passive"))
      (node (ref "X1") (pin "2") (pinfunction "GND_2") (pintype "passive"))
    )
    (net (code "89") (name "Net-(D1-A)") (class "Default")
      (node (ref "D1") (pin "1") (pinfunction "A_1") (pintype "passive"))
      (node (ref "L1") (pin "2") (pinfunction "2_2") (pintype "passive"))
      (node (ref "R2") (pin "1") (pinfunction "1_1") (pintype "passive"))
      (node (ref "T2") (pin "1") (pinfunction "1_1") (pintype "passive"))
      (node (ref "T3") (pin "1") (pinfunction "1_1") (pintype "passive"))
    )
    (net (code "90") (name "Net-(D3-K)") (class "Default")
      (node (ref "C1") (pin "1") (pinfunction "1_1") (pintype "passive"))
      (node (ref "D3") (pin "2") (pinfunction "K_2") (pintype "passive"))
      (node (ref "L1") (pin "1") (pinfunction "1_1") (pintype "passive"))
      (node (ref "U1") (pin "8") (pinfunction "PH_8") (pintype "passive"))
    )
    (net (code "91") (name "Net-(LED1-A)") (class "Default")
      (node (ref "LED1") (pin "1") (pinfunction "A_1") (pintype "passive"))
      (node (ref "R7") (pin "2") (pinfunction "2_2") (pintype "passive"))
    )
    (net (code "92") (name "Net-(LED2-K)") (class "Default")
      (node (ref "LED2") (pin "2") (pinfunction "K_2") (pintype "passive"))
      (node (ref "R8") (pin "1") (pinfunction "1_1") (pintype "passive"))
    )
    (net (code "93") (name "Net-(LED3-K)") (class "Default")
      (node (ref "LED3") (pin "2") (pinfunction "K_2") (pintype "passive"))
      (node (ref "R9") (pin "1") (pinfunction "1_1") (pintype "passive"))
    )
    (net (code "94") (name "Net-(LED4-K)") (class "Default")
      (node (ref "LED4") (pin "2") (pinfunction "K_2") (pintype "passive"))
      (node (ref "R10") (pin "1") (pinfunction "1_1") (pintype "passive"))
    )
    (net (code "95") (name "Net-(R4-Pad2)") (class "Default")
      (node (ref "R4") (pin "2") (pinfunction "2_2") (pintype "passive"))
      (node (ref "R5") (pin "1") (pinfunction "1_1") (pintype "passive"))
      (node (ref "R6") (pin "1") (pinfunction "1_1") (pintype "passive"))
    )
    (net (code "96") (name "Net-(U1-BOOT)") (class "Default")
      (node (ref "C1") (pin "2") (pinfunction "2_2") (pintype "passive"))
      (node (ref "U1") (pin "1") (pinfunction "BOOT_1") (pintype "passive"))
    )
    (net (code "97") (name "Net-(U1-VSENSE)") (class "Default")
      (node (ref "R2") (pin "2") (pinfunction "2_2") (pintype "passive"))
      (node (ref "R3") (pin "1") (pinfunction "1_1") (pintype "passive"))
      (node (ref "U1") (pin "4") (pinfunction "VSENSE_4") (pintype "passive"))
    )
    (net (code "98") (name "Net-(U11-BYP)") (class "Default")
      (node (ref "C2") (pin "2") (pinfunction "2_2") (pintype "passive"))
      (node (ref "U11") (pin "4") (pinfunction "BYP_4") (pintype "passive"))
    )
    (net (code "99") (name "Net-(U15-BOOT0{slash}VPP)") (class "Default")
      (node (ref "R19") (pin "2") (pinfunction "2_2") (pintype "passive"))
      (node (ref "U15") (pin "94") (pinfunction "BOOT0/VPP_94") (pintype "passive"))
    )
    (net (code "100") (name "Net-(U15-NRST)") (class "Default")
      (node (ref "C8") (pin "1") (pinfunction "1_1") (pintype "passive"))
      (node (ref "U15") (pin "14") (pinfunction "NRST_14") (pintype "passive"))
    )
    (net (code "101") (name "Net-(U15-PH0{slash}OSC_IN)") (class "Default")
      (node (ref "U15") (pin "12") (pinfunction "PH0/OSC_IN_12") (pintype "passive"))
      (node (ref "X1") (pin "3") (pinfunction "OSC2_3") (pintype "passive"))
    )
    (net (code "102") (name "Net-(U15-PH1{slash}OSC_OUT)") (class "Default")
      (node (ref "U15") (pin "13") (pinfunction "PH1/OSC_OUT_13") (pintype "passive"))
      (node (ref "X1") (pin "1") (pinfunction "OSC1_1") (pintype "passive"))
    )
    (net (code "103") (name "Net-(U15-VCAP1)") (class "Default")
      (node (ref "C6") (pin "2") (pinfunction "2_2") (pintype "passive"))
      (node (ref "U15") (pin "49") (pinfunction "VCAP1_49") (pintype "passive"))
    )
    (net (code "104") (name "Net-(U15-VCAP2)") (class "Default")
      (node (ref "C7") (pin "2") (pinfunction "2_2") (pintype "passive"))
      (node (ref "U15") (pin "73") (pinfunction "VCAP2_73") (pintype "passive"))
    )
    (net (code "105") (name "VCC_2S~6S") (class "Default")
      (node (ref "D2") (pin "1") (pinfunction "A_1") (pintype "passive"))
      (node (ref "R4") (pin "1") (pinfunction "1_1") (pintype "passive"))
      (node (ref "U8") (pin "1") (pinfunction "1_1") (pintype "passive"))
      (node (ref "U8") (pin "2") (pinfunction "2_2") (pintype "passive"))
    )
    (net (code "106") (name "VCC_3.3V") (class "Default")
      (node (ref "C5") (pin "2") (pinfunction "2_2") (pintype "passive"))
      (node (ref "R20") (pin "2") (pinfunction "2_2") (pintype "passive"))
      (node (ref "R7") (pin "1") (pinfunction "1_1") (pintype "passive"))
      (node (ref "T4") (pin "1") (pinfunction "1_1") (pintype "passive"))
      (node (ref "U10") (pin "1") (pinfunction "1_1") (pintype "passive"))
      (node (ref "U11") (pin "5") (pinfunction "OUT_5") (pintype "passive"))
      (node (ref "U15") (pin "100") (pinfunction "VDD_3_100") (pintype "passive"))
      (node (ref "U15") (pin "11") (pinfunction "VDD_5_11") (pintype "passive"))
      (node (ref "U15") (pin "19") (pinfunction "VDD_19") (pintype "passive"))
      (node (ref "U15") (pin "21") (pinfunction "VREF+_21") (pintype "passive"))
      (node (ref "U15") (pin "22") (pinfunction "VDDA_22") (pintype "passive"))
      (node (ref "U15") (pin "28") (pinfunction "VDD_4_28") (pintype "passive"))
      (node (ref "U15") (pin "50") (pinfunction "VDD_1_50") (pintype "passive"))
      (node (ref "U15") (pin "6") (pinfunction "VBAT_6") (pintype "passive"))
      (node (ref "U15") (pin "75") (pinfunction "VDD_2_75") (pintype "passive"))
      (node (ref "W1") (pin "3") (pinfunction "/WP_3") (pintype "passive"))
      (node (ref "W1") (pin "7") (pinfunction "/HOLD_7") (pintype "passive"))
      (node (ref "W1") (pin "8") (pinfunction "VCC_8") (pintype "passive"))
    )
    (net (code "107") (name "VCC_5.0V") (class "Default")
      (node (ref "C3") (pin "2") (pinfunction "2_2") (pintype "passive"))
      (node (ref "C4") (pin "2") (pinfunction "2_2") (pintype "passive"))
      (node (ref "D1") (pin "2") (pinfunction "K_2") (pintype "passive"))
      (node (ref "H2") (pin "1") (pinfunction "1_1") (pintype "passive"))
      (node (ref "H2") (pin "2") (pinfunction "2_2") (pintype "passive"))
      (node (ref "H2") (pin "3") (pinfunction "3_3") (pintype "passive"))
      (node (ref "H2") (pin "4") (pinfunction "4_4") (pintype "passive"))
      (node (ref "H2") (pin "5") (pinfunction "5_5") (pintype "passive"))
      (node (ref "H2") (pin "6") (pinfunction "6_6") (pintype "passive"))
      (node (ref "H2") (pin "7") (pinfunction "7_7") (pintype "passive"))
      (node (ref "H2") (pin "8") (pinfunction "8_8") (pintype "passive"))
      (node (ref "H4") (pin "8") (pinfunction "8_8") (pintype "passive"))
      (node (ref "LED2") (pin "1") (pinfunction "A_1") (pintype "passive"))
      (node (ref "LED3") (pin "1") (pinfunction "A_1") (pintype "passive"))
      (node (ref "LED4") (pin "1") (pinfunction "A_1") (pintype "passive"))
      (node (ref "P1") (pin "2") (pinfunction "2_2") (pintype "passive"))
      (node (ref "U11") (pin "1") (pinfunction "EN_1") (pintype "passive"))
      (node (ref "U11") (pin "3") (pinfunction "IN_3") (pintype "passive"))
      (node (ref "U2") (pin "1") (pinfunction "VDD_1") (pintype "passive"))
      (node (ref "U3") (pin "1") (pinfunction "1_1") (pintype "passive"))
      (node (ref "U4") (pin "1") (pinfunction "1_1") (pintype "passive"))
      (node (ref "U5") (pin "1") (pinfunction "1_1") (pintype "passive"))
      (node (ref "U6") (pin "1") (pinfunction "1_1") (pintype "passive"))
      (node (ref "U7") (pin "1") (pinfunction "1_1") (pintype "passive"))
      (node (ref "U9") (pin "2") (pinfunction "2_2") (pintype "passive"))
    )
    (net (code "108") (name "VCC_IN") (class "Default")
      (node (ref "D2") (pin "2") (pinfunction "K_2") (pintype "passive"))
      (node (ref "T1") (pin "1") (pinfunction "1_1") (pintype "passive"))
      (node (ref "U1") (pin "7") (pinfunction "VIN_7") (pintype "passive"))
    )
    (net (code "109") (name "unconnected-(U1-ENA-Pad5)") (class "Default")
      (node (ref "U1") (pin "5") (pinfunction "ENA_5") (pintype "passive"))
    )
    (net (code "110") (name "unconnected-(U1-NC-Pad2)") (class "Default")
      (node (ref "U1") (pin "2") (pinfunction "NC_2") (pintype "passive"))
    )
    (net (code "111") (name "unconnected-(U1-NC-Pad3)") (class "Default")
      (node (ref "U1") (pin "3") (pinfunction "NC_3") (pintype "passive"))
    )
    (net (code "112") (name "unconnected-(U2-NCC-Pad4)") (class "Default")
      (node (ref "U2") (pin "4") (pinfunction "NCC_4") (pintype "passive"))
    )
    (net (code "113") (name "unconnected-(U15-ETH_MDC{slash}ADC123_IN11{slash}PC1-Pad16)") (class "Default")
      (node (ref "U15") (pin "16") (pinfunction "ETH_MDC/ADC123_IN11/PC1_16") (pintype "passive"))
    )
    (net (code "114") (name "unconnected-(U15-ETH_RXD0{slash}ADC12_IN14{slash}PC4-Pad33)") (class "Default")
      (node (ref "U15") (pin "33") (pinfunction "ETH_RXD0/ADC12_IN14/PC4_33") (pintype "passive"))
    )
    (net (code "115") (name "unconnected-(U15-FSMC_A16{slash}USART3_CTS{slash}PD11-Pad58)") (class "Default")
      (node (ref "U15") (pin "58") (pinfunction "FSMC_A16/USART3_CTS/PD11_58") (pintype "passive"))
    )
    (net (code "116") (name "unconnected-(U15-FSMC_CLK{slash}USART2_CTS{slash}PD3-Pad84)") (class "Default")
      (node (ref "U15") (pin "84") (pinfunction "FSMC_CLK/USART2_CTS/PD3_84") (pintype "passive"))
    )
    (net (code "117") (name "unconnected-(U15-FSMC_D3{slash}CAN1_TX{slash}PD1-Pad82)") (class "Default")
      (node (ref "U15") (pin "82") (pinfunction "FSMC_D3/CAN1_TX/PD1_82") (pintype "passive"))
    )
    (net (code "118") (name "unconnected-(U15-FSMC_D4{slash}PE7-Pad38)") (class "Default")
      (node (ref "U15") (pin "38") (pinfunction "FSMC_D4/PE7_38") (pintype "passive"))
    )
    (net (code "119") (name "unconnected-(U15-FSMC_D5{slash}PE8-Pad39)") (class "Default")
      (node (ref "U15") (pin "39") (pinfunction "FSMC_D5/PE8_39") (pintype "passive"))
    )
    (net (code "120") (name "unconnected-(U15-FSMC_D7{slash}PE10-Pad41)") (class "Default")
      (node (ref "U15") (pin "41") (pinfunction "FSMC_D7/PE10_41") (pintype "passive"))
    )
    (net (code "121") (name "unconnected-(U15-FSMC_D9{slash}PE12-Pad43)") (class "Default")
      (node (ref "U15") (pin "43") (pinfunction "FSMC_D9/PE12_43") (pintype "passive"))
    )
    (net (code "122") (name "unconnected-(U15-FSMC_D12{slash}PE15-Pad46)") (class "Default")
      (node (ref "U15") (pin "46") (pinfunction "FSMC_D12/PE15_46") (pintype "passive"))
    )
    (net (code "123") (name "unconnected-(U15-FSMC_D13{slash}USART3_TX{slash}PD8-Pad55)") (class "Default")
      (node (ref "U15") (pin "55") (pinfunction "FSMC_D13/USART3_TX/PD8_55") (pintype "passive"))
    )
    (net (code "124") (name "unconnected-(U15-FSMC_D14{slash}USART3_RX{slash}PD9-Pad56)") (class "Default")
      (node (ref "U15") (pin "56") (pinfunction "FSMC_D14/USART3_RX/PD9_56") (pintype "passive"))
    )
    (net (code "125") (name "unconnected-(U15-FSMC_D15{slash}USART3_CK{slash}PD10_P_P-Pad57)") (class "Default")
      (node (ref "U15") (pin "57") (pinfunction "FSMC_D15/USART3_CK/PD10_P_P_57") (pintype "passive"))
    )
    (net (code "126") (name "unconnected-(U15-FSMC_NE1{slash}FSMC_NCE2{slash}PD7-Pad88)") (class "Default")
      (node (ref "U15") (pin "88") (pinfunction "FSMC_NE1/FSMC_NCE2/PD7_88") (pintype "passive"))
    )
    (net (code "127") (name "unconnected-(U15-FSMC_NOE{slash}USART2_RTS{slash}PD4-Pad85)") (class "Default")
      (node (ref "U15") (pin "85") (pinfunction "FSMC_NOE/USART2_RTS/PD4_85") (pintype "passive"))
    )
    (net (code "128") (name "unconnected-(U15-OTG_HS_ULPI_STP{slash}EVENTOUT{slash}PC0-Pad15)") (class "Default")
      (node (ref "U15") (pin "15") (pinfunction "OTG_HS_ULPI_STP/EVENTOUT/PC0_15") (pintype "passive"))
    )
    (net (code "129") (name "unconnected-(U15-PA8{slash}MCO1{slash}I2C3_SCL{slash}OTG_FS_SOF-Pad67)") (class "Default")
      (node (ref "U15") (pin "67") (pinfunction "PA8/MCO1/I2C3_SCL/OTG_FS_SOF_67") (pintype "passive"))
    )
    (net (code "130") (name "unconnected-(U15-PA15{slash}JTDI{slash}I2S3_WS-Pad77)") (class "Default")
      (node (ref "U15") (pin "77") (pinfunction "PA15/JTDI/I2S3_WS_77") (pintype "passive"))
    )
    (net (code "131") (name "unconnected-(U15-PB3{slash}JTDO{slash}SPI3_SCK{slash}I2S3_CK{slash}SPI1_SCK-Pad89)") (class "Default")
      (node (ref "U15") (pin "89") (pinfunction "PB3/JTDO/SPI3_SCK/I2S3_CK/SPI1_SCK_89") (pintype "passive"))
    )
    (net (code "132") (name "unconnected-(U15-PB4{slash}JNTRST{slash}SPI3_MISO{slash}SPI1_MISO{slash}I2S3ext_SD-Pad90)") (class "Default")
      (node (ref "U15") (pin "90") (pinfunction "PB4/JNTRST/SPI3_MISO/SPI1_MISO/I2S3ext_SD_90") (pintype "passive"))
    )
    (net (code "133") (name "unconnected-(U15-PB5{slash}CAN2_RX{slash}OTG_HS_ULPI_D7{slash}DCMI_D10{slash}I2S3_SD-Pad91)") (class "Default")
      (node (ref "U15") (pin "91") (pinfunction "PB5/CAN2_RX/OTG_HS_ULPI_D7/DCMI_D10/I2S3_SD_91") (pintype "passive"))
    )
    (net (code "134") (name "unconnected-(U15-PB6{slash}I2C1_SCL{slash}CAN2_TX{slash}OTG_FS_INTN{slash}DCMI_D5{slash}USART1_TX_2_2-Pad92)") (class "Default")
      (node (ref "U15") (pin "92") (pinfunction "PB6/I2C1_SCL/CAN2_TX/OTG_FS_INTN/DCMI_D5/USART1_TX_2_2_92") (pintype "passive"))
    )
    (net (code "135") (name "unconnected-(U15-PB7{slash}I2C1_SDA{slash}FSMC_NL{slash}DCMI_VSYNC{slash}USART1_RX-Pad93)") (class "Default")
      (node (ref "U15") (pin "93") (pinfunction "PB7/I2C1_SDA/FSMC_NL/DCMI_VSYNC/USART1_RX_93") (pintype "passive"))
    )
    (net (code "136") (name "unconnected-(U15-PB8{slash}SDIO_D4{slash}DCMI_D6{slash}OTG_FS_SCL{slash}I2C1_SCL{slash}CAN1_RX_95_95-Pad95)") (class "Default")
      (node (ref "U15") (pin "95") (pinfunction "PB8/SDIO_D4/DCMI_D6/OTG_FS_SCL/I2C1_SCL/CAN1_RX_95_95_95") (pintype "passive"))
    )
    (net (code "137") (name "unconnected-(U15-PB9{slash}I2S2_WS{slash}OTG_FS_SDA{slash}SDIO_D5{slash}DCMI_D7{slash}I2C1_SDA{slash}CAN1_TX-Pad96)") (class "Default")
      (node (ref "U15") (pin "96") (pinfunction "PB9/I2S2_WS/OTG_FS_SDA/SDIO_D5/DCMI_D7/I2C1_SDA/CAN1_TX_96") (pintype "passive"))
    )
    (net (code "138") (name "unconnected-(U15-PC14-OSC32_IN-Pad8)") (class "Default")
      (node (ref "U15") (pin "8") (pinfunction "PC14-OSC32_IN_8") (pintype "passive"))
    )
    (net (code "139") (name "unconnected-(U15-PC15-OSC32_OUT-Pad9)") (class "Default")
      (node (ref "U15") (pin "9") (pinfunction "PC15-OSC32_OUT_9") (pintype "passive"))
    )
    (net (code "140") (name "unconnected-(U15-SPI2_MISO{slash}OTG_HS_ULPI_DIR{slash}I2S2ext_SD{slash}ADC123_IN12{slash}PC2-Pad17)") (class "Default")
      (node (ref "U15") (pin "17") (pinfunction "SPI2_MISO/OTG_HS_ULPI_DIR/I2S2ext_SD/ADC123_IN12/PC2_17") (pintype "passive"))
    )
    (net (code "141") (name "unconnected-(U15-SPI2_MOSI{slash}I2S2_SD{slash}OTG_HS_ULPI_NXT{slash}ADC123_IN13{slash}PC3-Pad18)") (class "Default")
      (node (ref "U15") (pin "18") (pinfunction "SPI2_MOSI/I2S2_SD/OTG_HS_ULPI_NXT/ADC123_IN13/PC3_18") (pintype "passive"))
    )
    (net (code "142") (name "unconnected-(U15-TAMPER-RTC_AF1{slash}PC13-Pad7)") (class "Default")
      (node (ref "U15") (pin "7") (pinfunction "TAMPER-RTC_AF1/PC13_7") (pintype "passive"))
    )
    (net (code "143") (name "unconnected-(U15-TRACED0{slash}FSMC_A19{slash}PE3-Pad2)") (class "Default")
      (node (ref "U15") (pin "2") (pinfunction "TRACED0/FSMC_A19/PE3_2") (pintype "passive"))
    )
    (net (code "144") (name "unconnected-(U15-TRACED1{slash}FSMC_A20{slash}DCMI_D4{slash}PE4-Pad3)") (class "Default")
      (node (ref "U15") (pin "3") (pinfunction "TRACED1/FSMC_A20/DCMI_D4/PE4_3") (pintype "passive"))
    )
    (net (code "145") (name "unconnected-(U15-TRACED2{slash}FSMC_A21{slash}DCMI_D6{slash}PE5-Pad4)") (class "Default")
      (node (ref "U15") (pin "4") (pinfunction "TRACED2/FSMC_A21/DCMI_D6/PE5_4") (pintype "passive"))
    )
    (net (code "146") (name "unconnected-(U15-TRACED3{slash}FSMC_A22{slash}DCMI_D7{slash}PE6-Pad5)") (class "Default")
      (node (ref "U15") (pin "5") (pinfunction "TRACED3/FSMC_A22/DCMI_D7/PE6_5") (pintype "passive"))
    )
  )
)
